# SmartThermo1_7.net
KiCad netlist of a schematic drawn in EAGLE
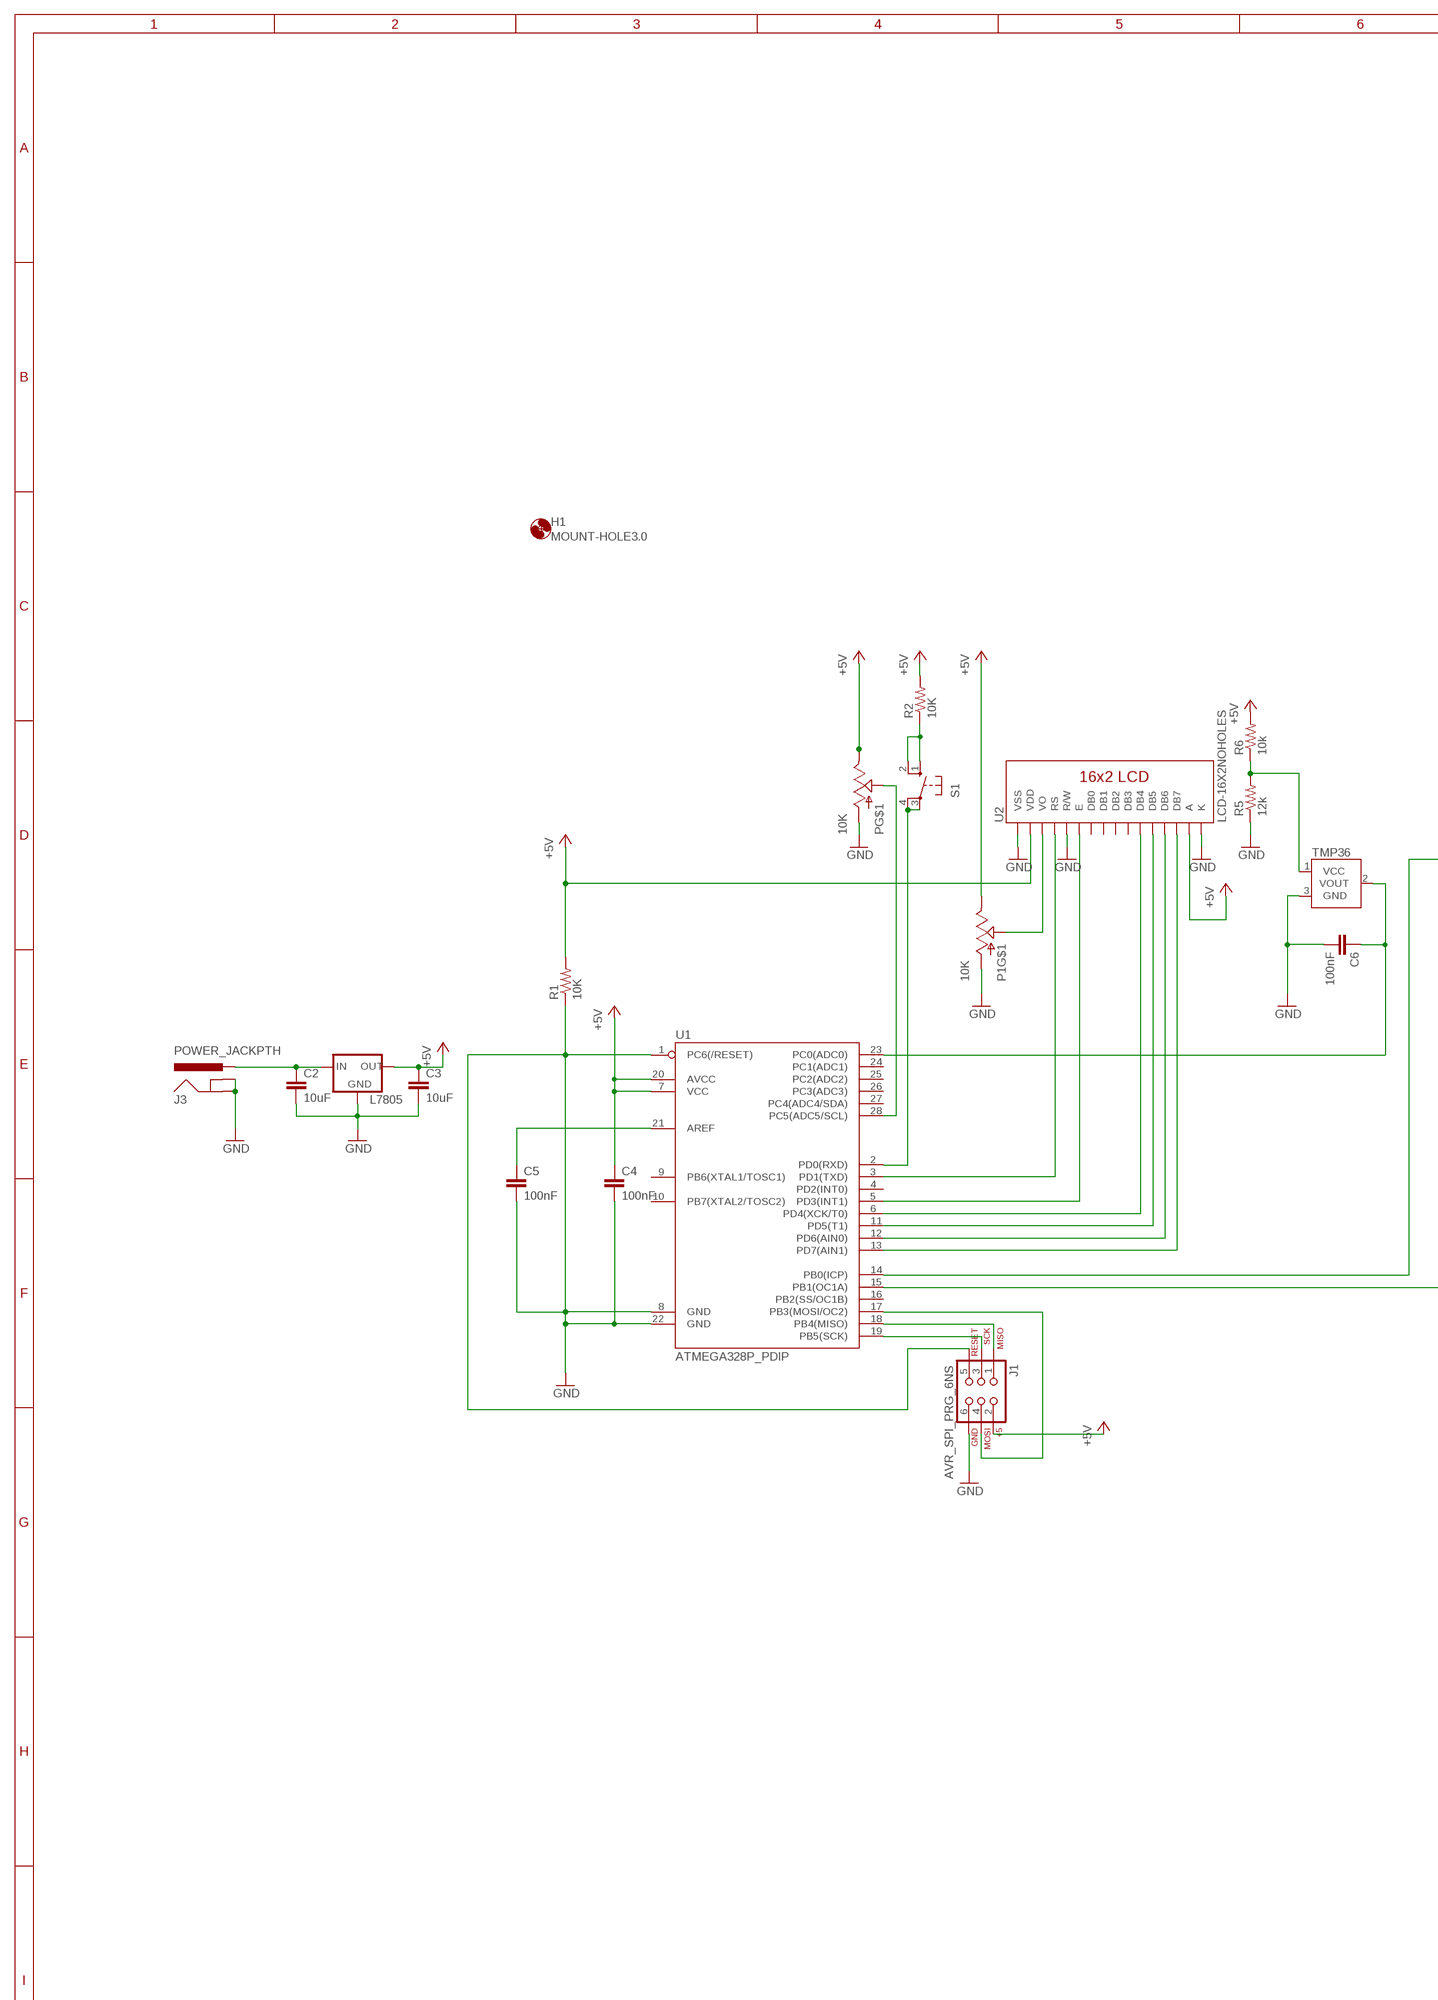
[diagram p0: schematic, sheet 1, part 1 of 2]
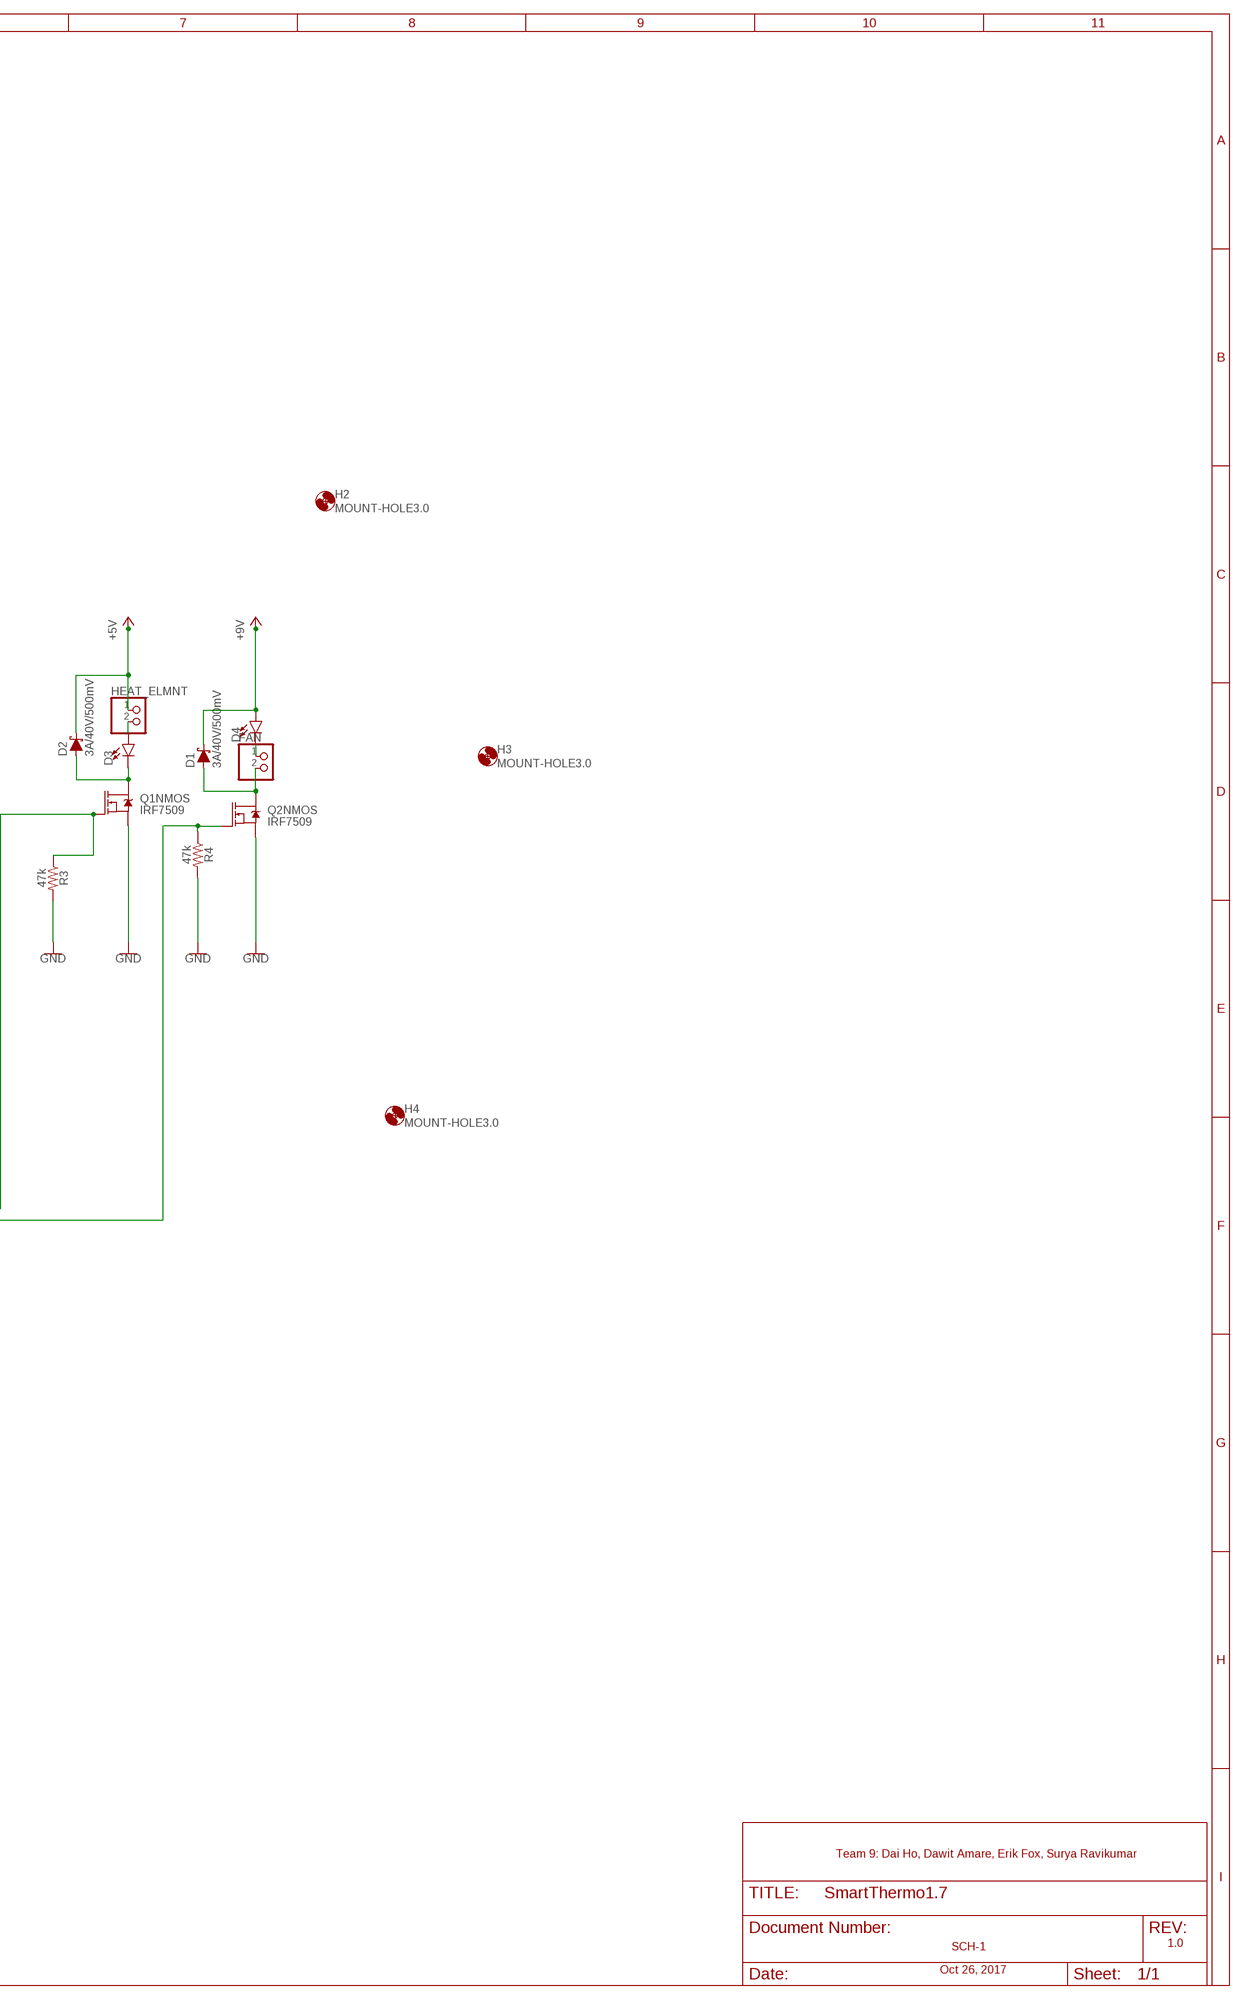
[diagram p1: schematic, sheet 1, part 2 of 2]

(export (version "E")
  (design (tool "Eeschema 10.0.6"))
  (components
    (comp (ref "C2")
      (value "10uF")
      (footprint "eagle-import:C7.5B3")
      (libsource (lib "eagle-import") (part "C7.5/3"))
    )
    (comp (ref "C3")
      (value "10uF")
      (footprint "eagle-import:C7.5B3")
      (libsource (lib "eagle-import") (part "C7.5/3"))
    )
    (comp (ref "C4")
      (value "100nF")
      (footprint "eagle-import:C2.5-2")
      (libsource (lib "eagle-import") (part "C2.5/2"))
    )
    (comp (ref "C5")
      (value "100nF")
      (footprint "eagle-import:C2.5-2")
      (libsource (lib "eagle-import") (part "C2.5/2"))
    )
    (comp (ref "C6")
      (value "100nF")
      (footprint "eagle-import:C2.5-2")
      (libsource (lib "eagle-import") (part "C2.5/2"))
    )
    (comp (ref "D1")
      (value "3A/40V/500mV")
      (footprint "eagle-import:SMA-DIODE")
      (libsource (lib "eagle-import") (part "DIODE-SCHOTTKY-B340A"))
    )
    (comp (ref "D2")
      (value "3A/40V/500mV")
      (footprint "eagle-import:SMA-DIODE")
      (libsource (lib "eagle-import") (part "DIODE-SCHOTTKY-B340A"))
    )
    (comp (ref "D3")
      (value "LED3MM")
      (footprint "eagle-import:LED_3MM")
      (libsource (lib "eagle-import") (part "LED3MM"))
    )
    (comp (ref "D4")
      (value "LED3MM")
      (footprint "eagle-import:LED_3MM")
      (libsource (lib "eagle-import") (part "LED3MM"))
    )
    (comp (ref "FAN")
      (value "PINHD-1X2/90")
      (footprint "eagle-import:1X02_90")
      (libsource (lib "eagle-import") (part "PINHD-1X2/90"))
    )
    (comp (ref "H1")
      (value "MOUNT-HOLE3.0")
      (footprint "eagle-import:3,0")
      (libsource (lib "eagle-import") (part "MOUNT-HOLE3.0"))
    )
    (comp (ref "H2")
      (value "MOUNT-HOLE3.0")
      (footprint "eagle-import:3,0")
      (libsource (lib "eagle-import") (part "MOUNT-HOLE3.0"))
    )
    (comp (ref "H3")
      (value "MOUNT-HOLE3.0")
      (footprint "eagle-import:3,0")
      (libsource (lib "eagle-import") (part "MOUNT-HOLE3.0"))
    )
    (comp (ref "H4")
      (value "MOUNT-HOLE3.0")
      (footprint "eagle-import:3,0")
      (libsource (lib "eagle-import") (part "MOUNT-HOLE3.0"))
    )
    (comp (ref "HEAT_ELMNT")
      (value "PINHD-1X2/90")
      (footprint "eagle-import:1X02_90")
      (libsource (lib "eagle-import") (part "PINHD-1X2/90"))
    )
    (comp (ref "J1")
      (value "AVR_SPI_PRG_6NS")
      (footprint "eagle-import:2X3-NS")
      (libsource (lib "eagle-import") (part "AVR_SPI_PRG_6NS"))
    )
    (comp (ref "J3")
      (value "POWER_JACKPTH")
      (footprint "eagle-import:POWER_JACK_PTH")
      (libsource (lib "eagle-import") (part "POWER_JACKPTH"))
    )
    (comp (ref "L7805")
      (value "78XXL")
      (footprint "eagle-import:78XXL")
      (libsource (lib "eagle-import") (part "78XXL"))
    )
    (comp (ref "P")
      (value "10K")
      (footprint "eagle-import:POT_PTH")
      (libsource (lib "eagle-import") (part "POT_SWITCHPOT_PTH"))
    )
    (comp (ref "P1")
      (value "10K")
      (footprint "eagle-import:POT_PTH")
      (libsource (lib "eagle-import") (part "POT_SWITCHPOT_PTH"))
    )
    (comp (ref "Q1")
      (value "IRF7509")
      (footprint "eagle-import:MSOP8")
      (libsource (lib "eagle-import") (part "IRF7509"))
    )
    (comp (ref "Q2")
      (value "IRF7509")
      (footprint "eagle-import:MSOP8")
      (libsource (lib "eagle-import") (part "IRF7509"))
    )
    (comp (ref "R1")
      (value "10K")
      (footprint "eagle-import:1206")
      (libsource (lib "eagle-import") (part "RESISTOR1206"))
    )
    (comp (ref "R2")
      (value "10K")
      (footprint "eagle-import:1206")
      (libsource (lib "eagle-import") (part "RESISTOR1206"))
    )
    (comp (ref "R3")
      (value "47k")
      (footprint "eagle-import:0603")
      (libsource (lib "eagle-import") (part "47KOHM-0603-1/10W-1%"))
    )
    (comp (ref "R4")
      (value "47k")
      (footprint "eagle-import:0603")
      (libsource (lib "eagle-import") (part "47KOHM-0603-1/10W-1%"))
    )
    (comp (ref "R5")
      (value "12k")
      (footprint "eagle-import:0204_5")
      (libsource (lib "eagle-import") (part "R-US_0204/5"))
    )
    (comp (ref "R6")
      (value "10k")
      (footprint "eagle-import:0204_5")
      (libsource (lib "eagle-import") (part "R-US_0204/5"))
    )
    (comp (ref "S1")
      (value "10-XX")
      (footprint "eagle-import:B3F-10XX")
      (fields (field (name "MPN") "B3F-1000"))
      (libsource (lib "eagle-import") (part "10-XX"))
    )
    (comp (ref "TMP36")
      (value "TMP36GT9")
      (footprint "eagle-import:TO-92")
      (libsource (lib "eagle-import") (part "TMP36GT9"))
    )
    (comp (ref "U1")
      (value "ATMEGA328P_PDIP")
      (footprint "eagle-import:DIL28-3")
      (libsource (lib "eagle-import") (part "ATMEGA328P_PDIP"))
    )
    (comp (ref "U2")
      (value "LCD-16X2NOHOLES")
      (footprint "eagle-import:LCD-16X2_NOHOLES")
      (libsource (lib "eagle-import") (part "LCD-16X2NOHOLES"))
    )
  )
  (nets
    (net (code "1") (name "+5V") (class "Default")
      (node (ref "C3") (pin "1") (pinfunction "1_1") (pintype "passive"))
      (node (ref "C4") (pin "1") (pinfunction "1_1") (pintype "passive"))
      (node (ref "D1") (pin "C") (pinfunction "C_C") (pintype "passive"))
      (node (ref "D2") (pin "C") (pinfunction "C_C") (pintype "passive"))
      (node (ref "D4") (pin "A") (pinfunction "A_A") (pintype "passive"))
      (node (ref "HEAT_ELMNT") (pin "1") (pinfunction "1_1") (pintype "passive"))
      (node (ref "J1") (pin "2") (pinfunction "2_2") (pintype "passive"))
      (node (ref "L7805") (pin "OUT") (pinfunction "OUT_OUT") (pintype "passive"))
      (node (ref "P") (pin "E@2") (pinfunction "E_E@2") (pintype "passive"))
      (node (ref "P1") (pin "E@2") (pinfunction "E_E@2") (pintype "passive"))
      (node (ref "R1") (pin "2") (pinfunction "2_2") (pintype "passive"))
      (node (ref "R2") (pin "2") (pinfunction "2_2") (pintype "passive"))
      (node (ref "R6") (pin "2") (pinfunction "2_2") (pintype "passive"))
      (node (ref "U1") (pin "20") (pinfunction "AVCC_20") (pintype "bidirectional"))
      (node (ref "U1") (pin "7") (pinfunction "VCC_7") (pintype "bidirectional"))
      (node (ref "U2") (pin "15") (pinfunction "A_15") (pintype "power_in"))
      (node (ref "U2") (pin "2") (pinfunction "VDD_2") (pintype "power_in"))
    )
    (net (code "2") (name "GND") (class "Default")
      (node (ref "C2") (pin "2") (pinfunction "2_2") (pintype "passive"))
      (node (ref "C3") (pin "2") (pinfunction "2_2") (pintype "passive"))
      (node (ref "C4") (pin "2") (pinfunction "2_2") (pintype "passive"))
      (node (ref "C5") (pin "2") (pinfunction "2_2") (pintype "passive"))
      (node (ref "C6") (pin "2") (pinfunction "2_2") (pintype "passive"))
      (node (ref "J1") (pin "5") (pinfunction "5_5") (pintype "passive"))
      (node (ref "J1") (pin "6") (pinfunction "6_6") (pintype "passive"))
      (node (ref "J3") (pin "GND") (pinfunction "GND_GND") (pintype "bidirectional"))
      (node (ref "J3") (pin "GNDBREAK") (pinfunction "GNDBREAK_GNDBREAK") (pintype "bidirectional"))
      (node (ref "L7805") (pin "GND") (pinfunction "GND_GND") (pintype "input"))
      (node (ref "P") (pin "E@1") (pinfunction "A_E@1") (pintype "passive"))
      (node (ref "P1") (pin "E@1") (pinfunction "A_E@1") (pintype "passive"))
      (node (ref "Q1") (pin "1") (pinfunction "S_1") (pintype "bidirectional"))
      (node (ref "Q2") (pin "1") (pinfunction "S_1") (pintype "bidirectional"))
      (node (ref "R1") (pin "1") (pinfunction "1_1") (pintype "passive"))
      (node (ref "R3") (pin "2") (pinfunction "2_2") (pintype "passive"))
      (node (ref "R4") (pin "2") (pinfunction "2_2") (pintype "passive"))
      (node (ref "R5") (pin "1") (pinfunction "1_1") (pintype "passive"))
      (node (ref "TMP36") (pin "3") (pinfunction "GND_3") (pintype "bidirectional"))
      (node (ref "U1") (pin "1") (pinfunction "PC6(/RESET)_1") (pintype "bidirectional"))
      (node (ref "U1") (pin "22") (pinfunction "GND_22") (pintype "bidirectional"))
      (node (ref "U1") (pin "8") (pinfunction "GND_8") (pintype "bidirectional"))
      (node (ref "U2") (pin "1") (pinfunction "VSS_1") (pintype "power_in"))
      (node (ref "U2") (pin "16") (pinfunction "K_16") (pintype "power_in"))
      (node (ref "U2") (pin "5") (pinfunction "R/W_5") (pintype "input"))
    )
    (net (code "3") (name "Net-(C2-Pad1)") (class "Default")
      (node (ref "C2") (pin "1") (pinfunction "1_1") (pintype "passive"))
      (node (ref "J3") (pin "PWR") (pinfunction "PWR_PWR") (pintype "bidirectional"))
      (node (ref "L7805") (pin "IN") (pinfunction "IN_IN") (pintype "input"))
    )
    (net (code "4") (name "Net-(D1-PadA)") (class "Default")
      (node (ref "D1") (pin "A") (pinfunction "A_A") (pintype "passive"))
      (node (ref "FAN") (pin "2") (pinfunction "2_2") (pintype "passive"))
      (node (ref "Q2") (pin "7") (pinfunction "D_7") (pintype "bidirectional"))
      (node (ref "Q2") (pin "8") (pinfunction "D_8") (pintype "bidirectional"))
    )
    (net (code "5") (name "Net-(D3-C)") (class "Default")
      (node (ref "D2") (pin "A") (pinfunction "A_A") (pintype "passive"))
      (node (ref "D3") (pin "K") (pinfunction "C_K") (pintype "passive"))
      (node (ref "Q1") (pin "7") (pinfunction "D_7") (pintype "bidirectional"))
      (node (ref "Q1") (pin "8") (pinfunction "D_8") (pintype "bidirectional"))
    )
    (net (code "6") (name "Net-(D3-PadA)") (class "Default")
      (node (ref "D3") (pin "A") (pinfunction "A_A") (pintype "passive"))
      (node (ref "HEAT_ELMNT") (pin "2") (pinfunction "2_2") (pintype "passive"))
    )
    (net (code "7") (name "Net-(D4-C)") (class "Default")
      (node (ref "D4") (pin "K") (pinfunction "C_K") (pintype "passive"))
      (node (ref "FAN") (pin "1") (pinfunction "1_1") (pintype "passive"))
    )
    (net (code "8") (name "Net-(P1A-S)") (class "Default")
      (node (ref "P1") (pin "WAND") (pinfunction "S_WAND") (pintype "passive"))
      (node (ref "U2") (pin "3") (pinfunction "VO_3") (pintype "bidirectional"))
    )
    (net (code "9") (name "Net-(PA-S)") (class "Default")
      (node (ref "P") (pin "WAND") (pinfunction "S_WAND") (pintype "passive"))
      (node (ref "U1") (pin "28") (pinfunction "PC5(ADC5/SCL)_28") (pintype "bidirectional"))
    )
    (net (code "10") (name "Net-(Q1A-G)") (class "Default")
      (node (ref "Q1") (pin "2") (pinfunction "G_2") (pintype "bidirectional"))
      (node (ref "R3") (pin "1") (pinfunction "1_1") (pintype "passive"))
      (node (ref "U1") (pin "14") (pinfunction "PB0(ICP)_14") (pintype "bidirectional"))
    )
    (net (code "11") (name "Net-(Q2A-G)") (class "Default")
      (node (ref "Q2") (pin "2") (pinfunction "G_2") (pintype "bidirectional"))
      (node (ref "R4") (pin "1") (pinfunction "1_1") (pintype "passive"))
      (node (ref "U1") (pin "15") (pinfunction "PB1(OC1A)_15") (pintype "bidirectional"))
    )
    (net (code "12") (name "Net-(S1-P)") (class "Default")
      (node (ref "S1") (pin "3") (pinfunction "P_3") (pintype "passive"))
      (node (ref "S1") (pin "4") (pinfunction "P1_4") (pintype "passive"))
      (node (ref "U1") (pin "2") (pinfunction "PD0(RXD)_2") (pintype "bidirectional"))
    )
    (net (code "13") (name "Net-(S1-S)") (class "Default")
      (node (ref "R2") (pin "1") (pinfunction "1_1") (pintype "passive"))
      (node (ref "S1") (pin "1") (pinfunction "S_1") (pintype "passive"))
      (node (ref "S1") (pin "2") (pinfunction "S1_2") (pintype "passive"))
    )
    (net (code "14") (name "Net-(TMP36-VCC)") (class "Default")
      (node (ref "R5") (pin "2") (pinfunction "2_2") (pintype "passive"))
      (node (ref "R6") (pin "1") (pinfunction "1_1") (pintype "passive"))
      (node (ref "TMP36") (pin "1") (pinfunction "VCC_1") (pintype "bidirectional"))
    )
    (net (code "15") (name "Net-(TMP36-VOUT)") (class "Default")
      (node (ref "C6") (pin "1") (pinfunction "1_1") (pintype "passive"))
      (node (ref "TMP36") (pin "2") (pinfunction "VOUT_2") (pintype "bidirectional"))
      (node (ref "U1") (pin "23") (pinfunction "PC0(ADC0)_23") (pintype "bidirectional"))
    )
    (net (code "16") (name "Net-(U1-AREF)") (class "Default")
      (node (ref "C5") (pin "1") (pinfunction "1_1") (pintype "passive"))
      (node (ref "U1") (pin "21") (pinfunction "AREF_21") (pintype "bidirectional"))
    )
    (net (code "17") (name "Net-(U1-PB3(MOSI{slash}OC2))") (class "Default")
      (node (ref "J1") (pin "4") (pinfunction "4_4") (pintype "passive"))
      (node (ref "U1") (pin "17") (pinfunction "PB3(MOSI/OC2)_17") (pintype "bidirectional"))
    )
    (net (code "18") (name "Net-(U1-PB4(MISO))") (class "Default")
      (node (ref "J1") (pin "1") (pinfunction "1_1") (pintype "passive"))
      (node (ref "U1") (pin "18") (pinfunction "PB4(MISO)_18") (pintype "bidirectional"))
    )
    (net (code "19") (name "Net-(U1-PB5(SCK))") (class "Default")
      (node (ref "J1") (pin "3") (pinfunction "3_3") (pintype "passive"))
      (node (ref "U1") (pin "19") (pinfunction "PB5(SCK)_19") (pintype "bidirectional"))
    )
    (net (code "20") (name "Net-(U1-PD1(TXD))") (class "Default")
      (node (ref "U1") (pin "3") (pinfunction "PD1(TXD)_3") (pintype "bidirectional"))
      (node (ref "U2") (pin "4") (pinfunction "RS_4") (pintype "input"))
    )
    (net (code "21") (name "Net-(U1-PD3(INT1))") (class "Default")
      (node (ref "U1") (pin "5") (pinfunction "PD3(INT1)_5") (pintype "bidirectional"))
      (node (ref "U2") (pin "6") (pinfunction "E_6") (pintype "input"))
    )
    (net (code "22") (name "Net-(U1-PD4(XCK{slash}T0))") (class "Default")
      (node (ref "U1") (pin "6") (pinfunction "PD4(XCK/T0)_6") (pintype "bidirectional"))
      (node (ref "U2") (pin "11") (pinfunction "DB4_11") (pintype "bidirectional"))
    )
    (net (code "23") (name "Net-(U1-PD5(T1))") (class "Default")
      (node (ref "U1") (pin "11") (pinfunction "PD5(T1)_11") (pintype "bidirectional"))
      (node (ref "U2") (pin "12") (pinfunction "DB5_12") (pintype "bidirectional"))
    )
    (net (code "24") (name "Net-(U1-PD6(AIN0))") (class "Default")
      (node (ref "U1") (pin "12") (pinfunction "PD6(AIN0)_12") (pintype "bidirectional"))
      (node (ref "U2") (pin "13") (pinfunction "DB6_13") (pintype "bidirectional"))
    )
    (net (code "25") (name "Net-(U1-PD7(AIN1))") (class "Default")
      (node (ref "U1") (pin "13") (pinfunction "PD7(AIN1)_13") (pintype "bidirectional"))
      (node (ref "U2") (pin "14") (pinfunction "DB7_14") (pintype "bidirectional"))
    )
    (net (code "26") (name "unconnected-(U1-PB2(SS{slash}OC1B)-Pad16)") (class "Default")
      (node (ref "U1") (pin "16") (pinfunction "PB2(SS/OC1B)_16") (pintype "bidirectional"))
    )
    (net (code "27") (name "unconnected-(U1-PB6(XTAL1{slash}TOSC1)-Pad9)") (class "Default")
      (node (ref "U1") (pin "9") (pinfunction "PB6(XTAL1/TOSC1)_9") (pintype "bidirectional"))
    )
    (net (code "28") (name "unconnected-(U1-PB7(XTAL2{slash}TOSC2)-Pad10)") (class "Default")
      (node (ref "U1") (pin "10") (pinfunction "PB7(XTAL2/TOSC2)_10") (pintype "bidirectional"))
    )
    (net (code "29") (name "unconnected-(U1-PC1(ADC1)-Pad24)") (class "Default")
      (node (ref "U1") (pin "24") (pinfunction "PC1(ADC1)_24") (pintype "bidirectional"))
    )
    (net (code "30") (name "unconnected-(U1-PC2(ADC2)-Pad25)") (class "Default")
      (node (ref "U1") (pin "25") (pinfunction "PC2(ADC2)_25") (pintype "bidirectional"))
    )
    (net (code "31") (name "unconnected-(U1-PC3(ADC3)-Pad26)") (class "Default")
      (node (ref "U1") (pin "26") (pinfunction "PC3(ADC3)_26") (pintype "bidirectional"))
    )
    (net (code "32") (name "unconnected-(U1-PC4(ADC4{slash}SDA)-Pad27)") (class "Default")
      (node (ref "U1") (pin "27") (pinfunction "PC4(ADC4/SDA)_27") (pintype "bidirectional"))
    )
    (net (code "33") (name "unconnected-(U1-PD2(INT0)-Pad4)") (class "Default")
      (node (ref "U1") (pin "4") (pinfunction "PD2(INT0)_4") (pintype "bidirectional"))
    )
    (net (code "34") (name "unconnected-(U2-DB0-Pad7)") (class "Default")
      (node (ref "U2") (pin "7") (pinfunction "DB0_7") (pintype "bidirectional"))
    )
    (net (code "35") (name "unconnected-(U2-DB1-Pad8)") (class "Default")
      (node (ref "U2") (pin "8") (pinfunction "DB1_8") (pintype "bidirectional"))
    )
    (net (code "36") (name "unconnected-(U2-DB2-Pad9)") (class "Default")
      (node (ref "U2") (pin "9") (pinfunction "DB2_9") (pintype "bidirectional"))
    )
    (net (code "37") (name "unconnected-(U2-DB3-Pad10)") (class "Default")
      (node (ref "U2") (pin "10") (pinfunction "DB3_10") (pintype "bidirectional"))
    )
  )
)
